# P04_Processor_2_or_3_USB_and_Serial.net
KiCad netlist of a schematic drawn in Altium Designer
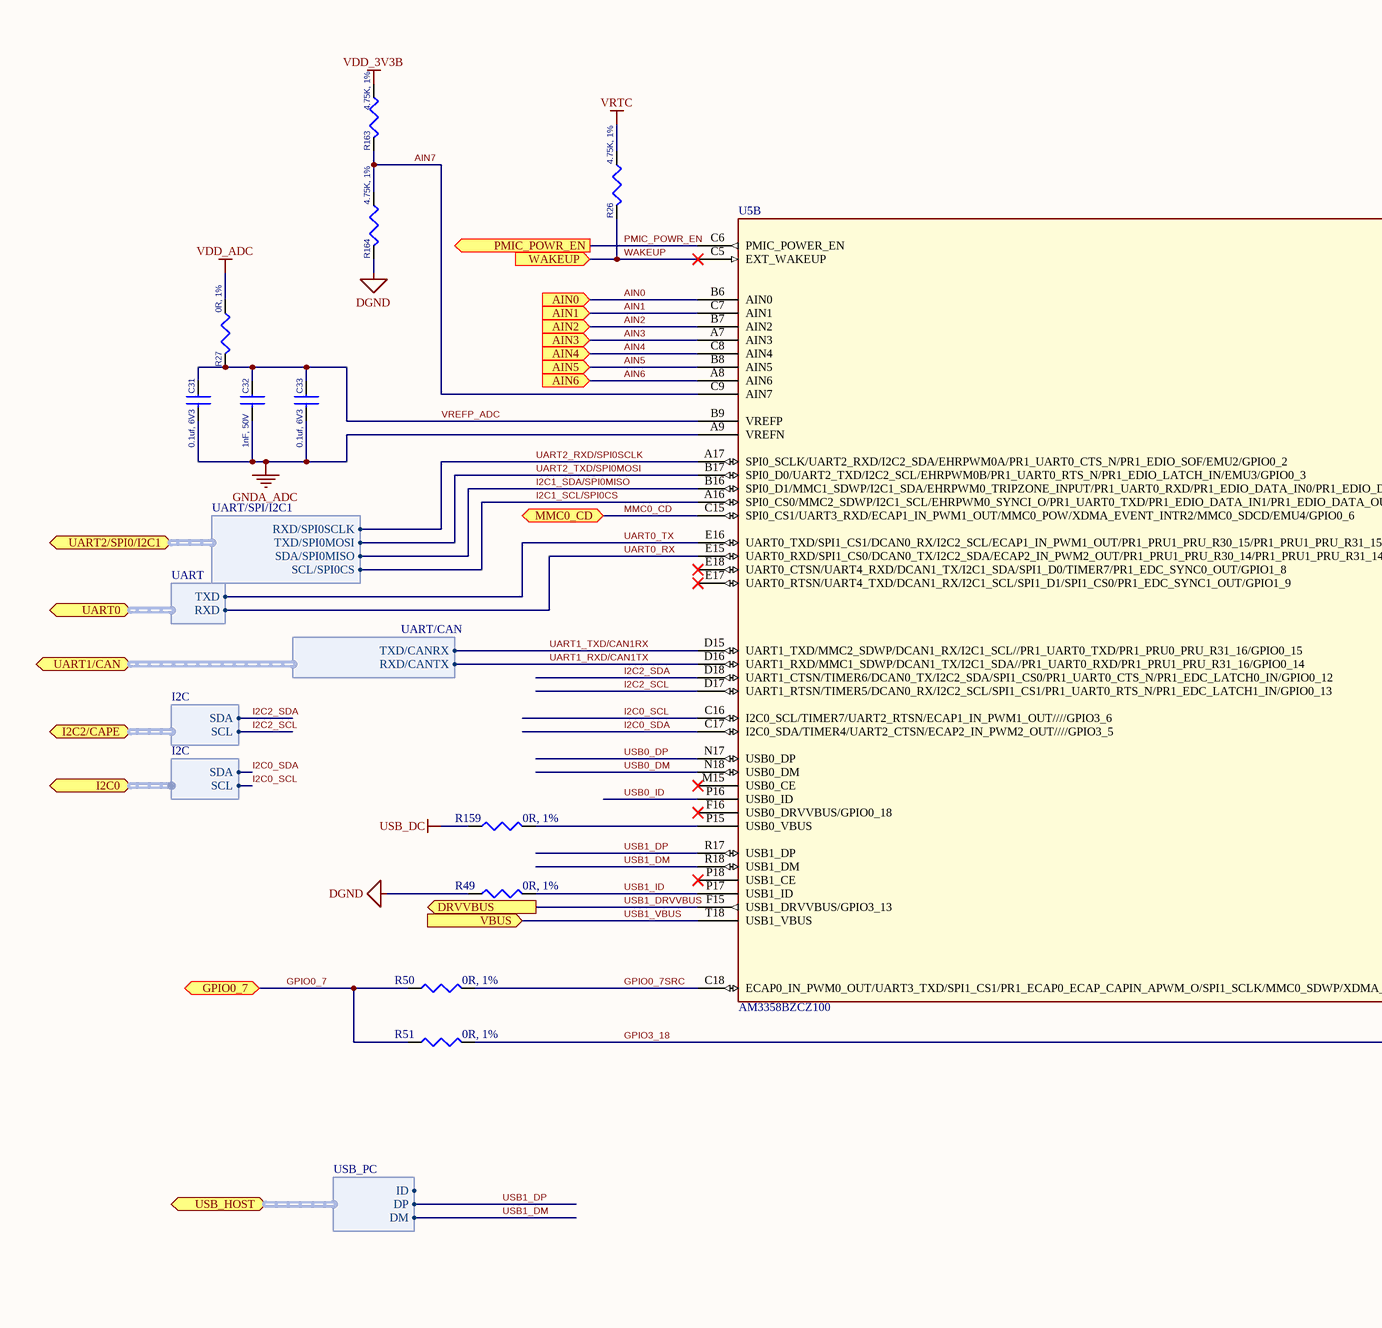
[diagram p0: P04_Processor 2 or 3, USB and Serial.SchDoc, left]
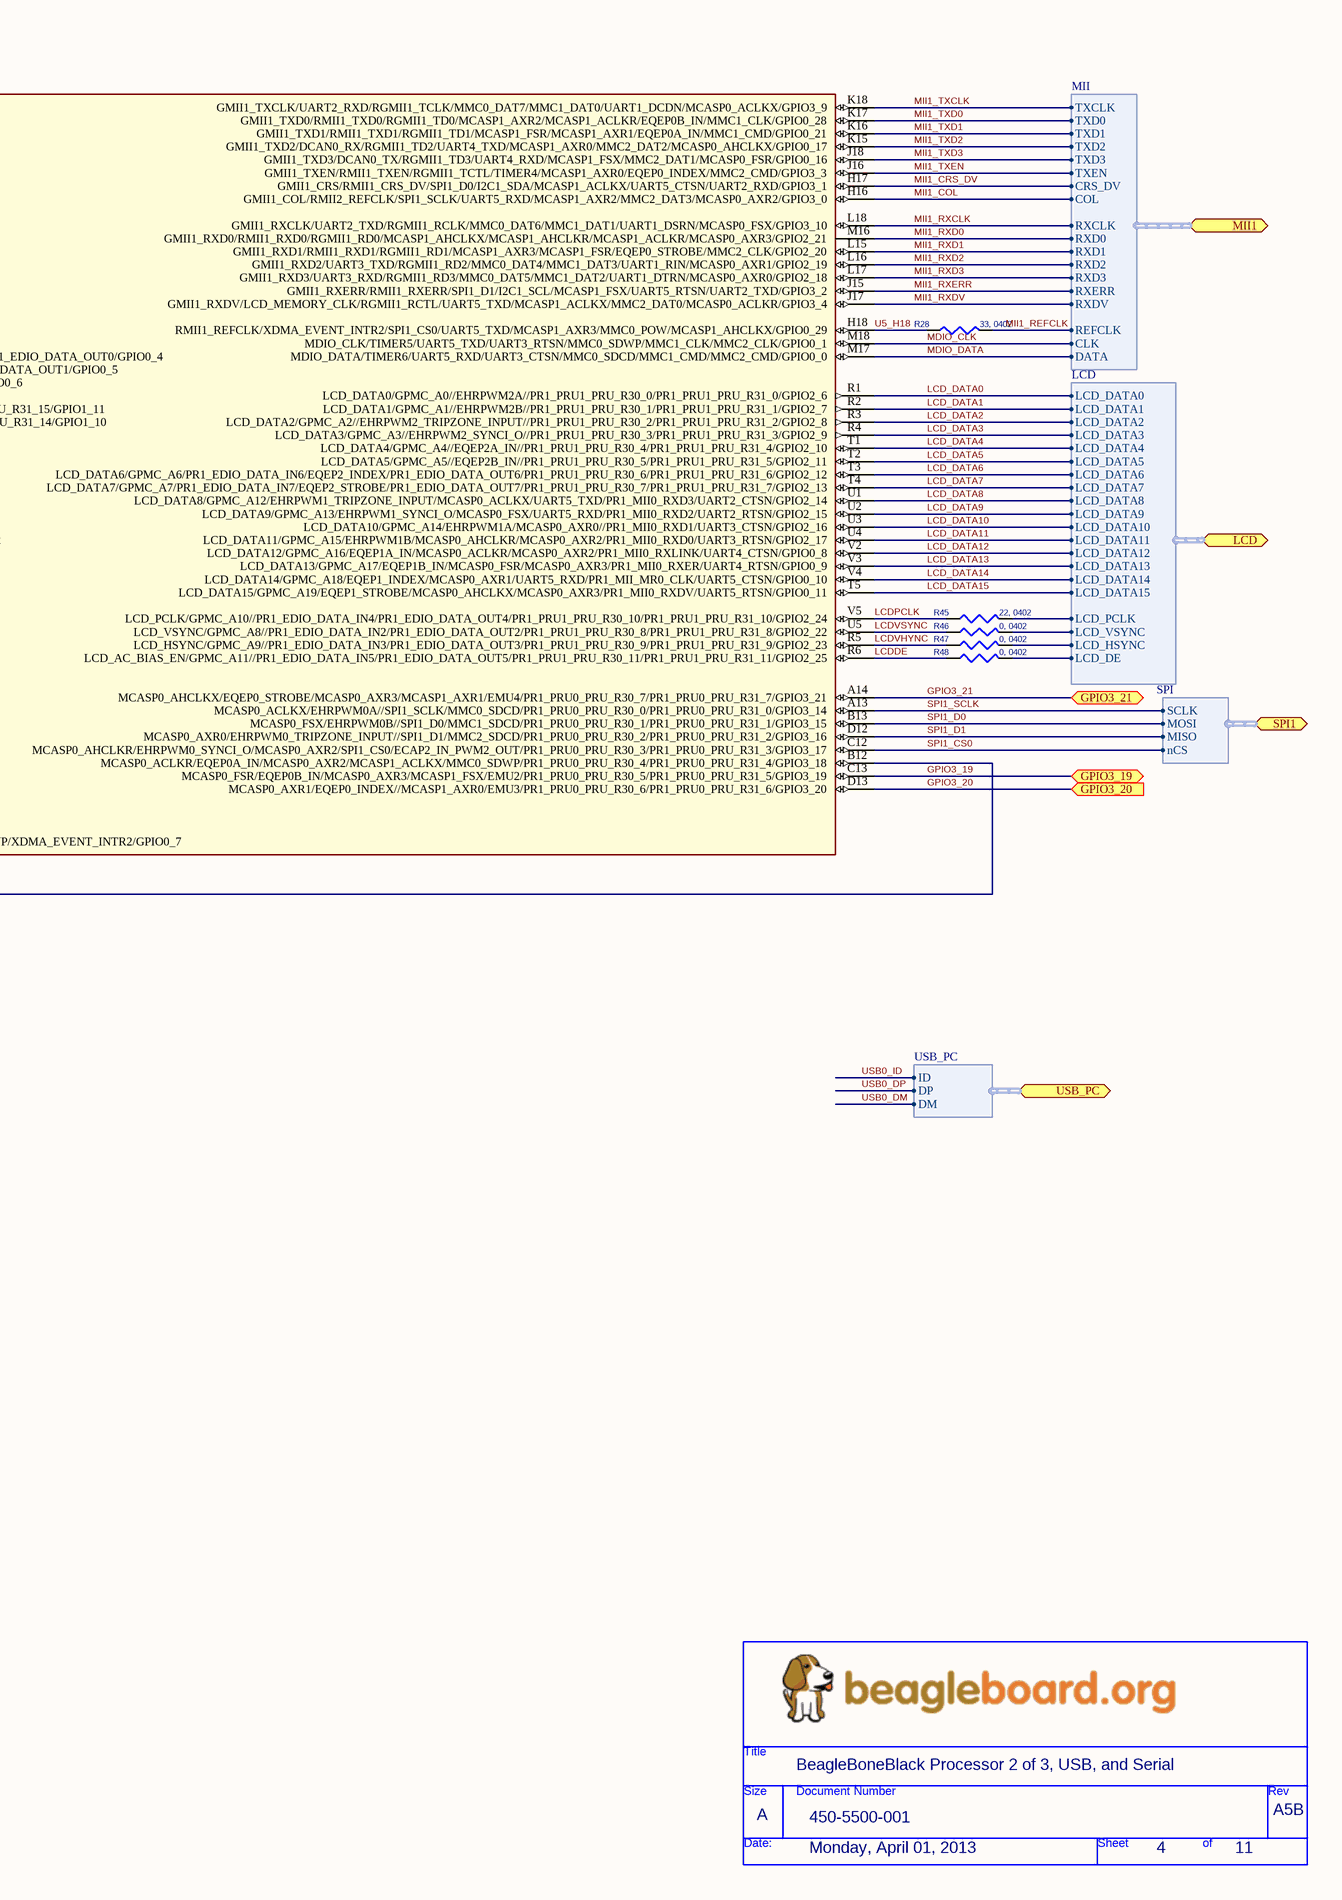
[diagram p1: P04_Processor 2 or 3, USB and Serial.SchDoc, right]

(export (version "E")
  (design (tool "Eeschema 10.0.6"))
  (components
    (comp (ref "C31")
      (value "0.1uf, 6V3")
      (footprint "402")
      (description "CAP CER 0.1UF 6.3V 10% X5R 0402")
      (fields
        (field (name "MANUFACTURER") "TDK Corporation")
        (field (name "MANUFACTURER PART NUMBER") "C1005X5R0J104K050BA")
      )
      (libsource (lib "BEAGLEBONEBLACK_REV A5B") (part "CAP_0.1uF_X7R_16V_10% 0402"))
    )
    (comp (ref "C32")
      (value "1nF, 50V")
      (footprint "402")
      (description "CAP CER 1000PF 16V 10% X7R 0402")
      (fields
        (field (name "MANUFACTURER") "Yageo")
        (field (name "MANUFACTURER PART NUMBER") "CC0402KRX7R7BB102")
      )
      (libsource (lib "BEAGLEBONEBLACK_REV A5B") (part "CAP_0.001_X7R_50V_5%_0402"))
    )
    (comp (ref "C33")
      (value "0.1uf, 6V3")
      (footprint "402")
      (description "CAP CER 0.1UF 6.3V 10% X5R 0402")
      (fields
        (field (name "MANUFACTURER") "TDK Corporation")
        (field (name "MANUFACTURER PART NUMBER") "C1005X5R0J104K050BA")
      )
      (libsource (lib "BEAGLEBONEBLACK_REV A5B") (part "CAP_0.1uF_X7R_16V_10% 0402"))
    )
    (comp (ref "R26")
      (value "4.75K, 1%")
      (footprint "402")
      (description "RES 4.75K OHM 1/16W 1% 0402 SMD")
      (fields
        (field (name "MANUFACTURER") "Stackpole Electronics Inc")
        (field (name "MANUFACTURER PART NUMBER") "RMCF0402FT4K75")
      )
      (libsource (lib "BEAGLEBONEBLACK_REV A5B") (part "RES_4.75K_1/16W_1%_0402"))
    )
    (comp (ref "R27")
      (value "0R, 1%")
      (footprint "402")
      (description "RES 0.0 OHM 1/16W 0402 SMD")
      (fields
        (field (name "MANUFACTURER") "Yageo")
        (field (name "MANUFACTURER PART NUMBER") "RC0402JR-070RL")
      )
      (libsource (lib "BEAGLEBONEBLACK_REV A5B") (part "RES_0_1/16W_1%_0402"))
    )
    (comp (ref "R28")
      (value "33, 0402")
      (footprint "402")
      (description "RES 33 OHM 1/16W 5% 0402 SMD")
      (fields
        (field (name "MANUFACTURER") "Panasonic Electronic Components")
        (field (name "MANUFACTURER PART NUMBER") "ERJ-2GEJ330X")
      )
      (libsource (lib "BEAGLEBONEBLACK_REV A5B") (part "RES_33_0402"))
    )
    (comp (ref "R45")
      (value "22, 0402")
      (footprint "402")
      (description "RES 22 OHM 1/16W 5% 0402 SMD")
      (fields
        (field (name "MANUFACTURER") "Panasonic Electronic Components")
        (field (name "MANUFACTURER PART NUMBER") "ERJ-2GEJ330X")
      )
      (libsource (lib "BEAGLEBONEBLACK_REV A5B") (part "RES_33_0402"))
    )
    (comp (ref "R46")
      (value "0, 0402")
      (footprint "402")
      (description "RES 0 OHM 1/16W 5% 0402 SMD")
      (fields
        (field (name "MANUFACTURER") "Panasonic Electronic Components")
        (field (name "MANUFACTURER PART NUMBER") "ERJ-2GEJ330X")
      )
      (libsource (lib "BEAGLEBONEBLACK_REV A5B") (part "RES_33_0402"))
    )
    (comp (ref "R47")
      (value "0, 0402")
      (footprint "402")
      (description "RES 0 OHM 1/16W 5% 0402 SMD")
      (fields
        (field (name "MANUFACTURER") "Panasonic Electronic Components")
        (field (name "MANUFACTURER PART NUMBER") "ERJ-2GEJ330X")
      )
      (libsource (lib "BEAGLEBONEBLACK_REV A5B") (part "RES_33_0402"))
    )
    (comp (ref "R48")
      (value "0, 0402")
      (footprint "402")
      (description "RES 0 OHM 1/16W 5% 0402 SMD")
      (fields
        (field (name "MANUFACTURER") "Panasonic Electronic Components")
        (field (name "MANUFACTURER PART NUMBER") "ERJ-2GEJ330X")
      )
      (libsource (lib "BEAGLEBONEBLACK_REV A5B") (part "RES_33_0402"))
    )
    (comp (ref "R49")
      (value "0R, 1%")
      (footprint "402")
      (description "RES 0.0 OHM 1/16W 0402 SMD")
      (fields
        (field (name "MANUFACTURER") "Yageo")
        (field (name "MANUFACTURER PART NUMBER") "RC0402JR-070RL")
      )
      (libsource (lib "BEAGLEBONEBLACK_REV A5B") (part "RES_0_1/16W_1%_0402"))
    )
    (comp (ref "R50")
      (value "0R, 1%")
      (footprint "402")
      (description "RES 0.0 OHM 1/16W 0402 SMD")
      (fields
        (field (name "MANUFACTURER") "Yageo")
        (field (name "MANUFACTURER PART NUMBER") "RC0402JR-070RL")
      )
      (libsource (lib "BEAGLEBONEBLACK_REV A5B") (part "RES_0_1/16W_1%_0402"))
    )
    (comp (ref "R51")
      (value "0R, 1%")
      (footprint "402")
      (description "RES 0.0 OHM 1/16W 0402 SMD")
      (fields
        (field (name "MANUFACTURER") "Yageo")
        (field (name "MANUFACTURER PART NUMBER") "RC0402JR-070RL")
      )
      (libsource (lib "BEAGLEBONEBLACK_REV A5B") (part "RES_0_1/16W_1%_0402"))
    )
    (comp (ref "R159")
      (value "0R, 1%")
      (footprint "402")
      (description "RES 0.0 OHM 1/16W 0402 SMD")
      (fields
        (field (name "MANUFACTURER") "Yageo")
        (field (name "MANUFACTURER PART NUMBER") "RC0402JR-070RL")
      )
      (libsource (lib "BEAGLEBONEBLACK_REV A5B") (part "RES_0_1/16W_1%_0402"))
    )
    (comp (ref "R163")
      (value "4.75K, 1%")
      (footprint "402")
      (description "RES 4.75K OHM 1/16W 1% 0402 SMD")
      (fields
        (field (name "MANUFACTURER") "Stackpole Electronics Inc")
        (field (name "MANUFACTURER PART NUMBER") "RMCF0402FT4K75")
      )
      (libsource (lib "BEAGLEBONEBLACK_REV A5B") (part "RES_4.75K_1/16W_1%_0402"))
    )
    (comp (ref "R164")
      (value "4.75K, 1%")
      (footprint "402")
      (description "RES 4.75K OHM 1/16W 1% 0402 SMD")
      (fields
        (field (name "MANUFACTURER") "Stackpole Electronics Inc")
        (field (name "MANUFACTURER PART NUMBER") "RMCF0402FT4K75")
      )
      (libsource (lib "BEAGLEBONEBLACK_REV A5B") (part "RES_4.75K_1/16W_1%_0402"))
    )
    (comp (ref "U5")
      (value "AM3358BZCZ100")
      (footprint "am33xx_15x15")
      (description "IC MPU SITARA 1.0GHZ 324NFBGA")
      (fields (field (name "MFR") "TI") (field (name "TIINTPARTNUMBER") "1A0242"))
      (libsource (lib "BEAGLEBONEBLACK_REV A5B") (part "IC_AM335X_ZCE_1"))
    )
  )
  (nets
    (net (code "9") (name "/AIN0") (class "Default")
      (node (ref "U5") (pin "B6") (pinfunction "AIN0_B6") (pintype "passive"))
    )
    (net (code "10") (name "/AIN1") (class "Default")
      (node (ref "U5") (pin "C7") (pinfunction "AIN1_C7") (pintype "passive"))
    )
    (net (code "11") (name "/AIN2") (class "Default")
      (node (ref "U5") (pin "B7") (pinfunction "AIN2_B7") (pintype "passive"))
    )
    (net (code "12") (name "/AIN3") (class "Default")
      (node (ref "U5") (pin "A7") (pinfunction "AIN3_A7") (pintype "passive"))
    )
    (net (code "13") (name "/AIN4") (class "Default")
      (node (ref "U5") (pin "C8") (pinfunction "AIN4_C8") (pintype "passive"))
    )
    (net (code "14") (name "/AIN5") (class "Default")
      (node (ref "U5") (pin "B8") (pinfunction "AIN5_B8") (pintype "passive"))
    )
    (net (code "15") (name "/AIN6") (class "Default")
      (node (ref "U5") (pin "A8") (pinfunction "AIN6_A8") (pintype "passive"))
    )
    (net (code "16") (name "/AIN7") (class "Default")
      (node (ref "R163") (pin "2") (pinfunction "2_2") (pintype "passive"))
      (node (ref "R164") (pin "1") (pinfunction "1_1") (pintype "passive"))
      (node (ref "U5") (pin "C9") (pinfunction "AIN7_C9") (pintype "passive"))
    )
    (net (code "17") (name "/GPIO0_7") (class "Default")
      (node (ref "R50") (pin "1") (pinfunction "1_1") (pintype "passive"))
      (node (ref "R51") (pin "1") (pinfunction "1_1") (pintype "passive"))
    )
    (net (code "18") (name "/GPIO0_7SRC") (class "Default")
      (node (ref "R50") (pin "2") (pinfunction "2_2") (pintype "passive"))
      (node (ref "U5") (pin "C18") (pinfunction "ECAP0_IN_PWM0_OUT/UART3_TXD/SPI1_CS1/PR1_ECAP0_ECAP_CAPIN_APWM_O/SPI1_SCLK/MMC0_SDWP/XDMA_EVENT_INTR2/GPIO0_7_C18") (pintype "bidirectional"))
    )
    (net (code "19") (name "/GPIO3_18") (class "Default")
      (node (ref "R51") (pin "2") (pinfunction "2_2") (pintype "passive"))
      (node (ref "U5") (pin "B12") (pinfunction "MCASP0_ACLKR/EQEP0A_IN/MCASP0_AXR2/MCASP1_ACLKX/MMC0_SDWP/PR1_PRU0_PRU_R30_4/PR1_PRU0_PRU_R31_4/GPIO3_18_B12") (pintype "bidirectional"))
    )
    (net (code "20") (name "/GPIO3_19") (class "Default")
      (node (ref "U5") (pin "C13") (pinfunction "MCASP0_FSR/EQEP0B_IN/MCASP0_AXR3/MCASP1_FSX/EMU2/PR1_PRU0_PRU_R30_5/PR1_PRU0_PRU_R31_5/GPIO3_19_C13") (pintype "bidirectional"))
    )
    (net (code "21") (name "/GPIO3_20") (class "Default")
      (node (ref "U5") (pin "D13") (pinfunction "MCASP0_AXR1/EQEP0_INDEX//MCASP1_AXR0/EMU3/PR1_PRU0_PRU_R30_6/PR1_PRU0_PRU_R31_6/GPIO3_20_D13") (pintype "bidirectional"))
    )
    (net (code "22") (name "/GPIO3_21") (class "Default")
      (node (ref "U5") (pin "A14") (pinfunction "MCASP0_AHCLKX/EQEP0_STROBE/MCASP0_AXR3/MCASP1_AXR1/EMU4/PR1_PRU0_PRU_R30_7/PR1_PRU0_PRU_R31_7/GPIO3_21_A14") (pintype "bidirectional"))
    )
    (net (code "23") (name "/I2C0_SCL") (class "Default")
      (node (ref "U5") (pin "C16") (pinfunction "I2C0_SCL/TIMER7/UART2_RTSN/ECAP1_IN_PWM1_OUT////GPIO3_6_C16") (pintype "bidirectional"))
    )
    (net (code "24") (name "/I2C0_SDA") (class "Default")
      (node (ref "U5") (pin "C17") (pinfunction "I2C0_SDA/TIMER4/UART2_CTSN/ECAP2_IN_PWM2_OUT////GPIO3_5_C17") (pintype "bidirectional"))
    )
    (net (code "25") (name "/I2C1_SCL{slash}SPI0CS") (class "Default")
      (node (ref "U5") (pin "A16") (pinfunction "SPI0_CS0/MMC2_SDWP/I2C1_SCL/EHRPWM0_SYNCI_O/PR1_UART0_TXD/PR1_EDIO_DATA_IN1/PR1_EDIO_DATA_OUT1/GPIO0_5_A16") (pintype "bidirectional"))
    )
    (net (code "26") (name "/I2C1_SDA{slash}SPI0MISO") (class "Default")
      (node (ref "U5") (pin "B16") (pinfunction "SPI0_D1/MMC1_SDWP/I2C1_SDA/EHRPWM0_TRIPZONE_INPUT/PR1_UART0_RXD/PR1_EDIO_DATA_IN0/PR1_EDIO_DATA_OUT0/GPIO0_4_B16") (pintype "bidirectional"))
    )
    (net (code "27") (name "/I2C2_SCL") (class "Default")
      (node (ref "U5") (pin "D17") (pinfunction "UART1_RTSN/TIMER5/DCAN0_RX/I2C2_SCL/SPI1_CS1/PR1_UART0_RTS_N/PR1_EDC_LATCH1_IN/GPIO0_13_D17") (pintype "bidirectional"))
    )
    (net (code "28") (name "/I2C2_SDA") (class "Default")
      (node (ref "U5") (pin "D18") (pinfunction "UART1_CTSN/TIMER6/DCAN0_TX/I2C2_SDA/SPI1_CS0/PR1_UART0_CTS_N/PR1_EDC_LATCH0_IN/GPIO0_12_D18") (pintype "bidirectional"))
    )
    (net (code "29") (name "/LCDDE") (class "Default")
      (node (ref "R48") (pin "1") (pinfunction "1_1") (pintype "passive"))
      (node (ref "U5") (pin "R6") (pinfunction "LCD_AC_BIAS_EN/GPMC_A11//PR1_EDIO_DATA_IN5/PR1_EDIO_DATA_OUT5/PR1_PRU1_PRU_R30_11/PR1_PRU1_PRU_R31_11/GPIO2_25_R6") (pintype "bidirectional"))
    )
    (net (code "30") (name "/LCDPCLK") (class "Default")
      (node (ref "R45") (pin "1") (pinfunction "1_1") (pintype "passive"))
      (node (ref "U5") (pin "V5") (pinfunction "LCD_PCLK/GPMC_A10//PR1_EDIO_DATA_IN4/PR1_EDIO_DATA_OUT4/PR1_PRU1_PRU_R30_10/PR1_PRU1_PRU_R31_10/GPIO2_24_V5") (pintype "bidirectional"))
    )
    (net (code "31") (name "/LCDVHYNC") (class "Default")
      (node (ref "R47") (pin "1") (pinfunction "1_1") (pintype "passive"))
      (node (ref "U5") (pin "R5") (pinfunction "LCD_HSYNC/GPMC_A9//PR1_EDIO_DATA_IN3/PR1_EDIO_DATA_OUT3/PR1_PRU1_PRU_R30_9/PR1_PRU1_PRU_R31_9/GPIO2_23_R5") (pintype "bidirectional"))
    )
    (net (code "32") (name "/LCDVSYNC") (class "Default")
      (node (ref "R46") (pin "1") (pinfunction "1_1") (pintype "passive"))
      (node (ref "U5") (pin "U5") (pinfunction "LCD_VSYNC/GPMC_A8//PR1_EDIO_DATA_IN2/PR1_EDIO_DATA_OUT2/PR1_PRU1_PRU_R30_8/PR1_PRU1_PRU_R31_8/GPIO2_22_U5") (pintype "bidirectional"))
    )
    (net (code "33") (name "/LCD_DATA0") (class "Default")
      (node (ref "U5") (pin "R1") (pinfunction "LCD_DATA0/GPMC_A0//EHRPWM2A//PR1_PRU1_PRU_R30_0/PR1_PRU1_PRU_R31_0/GPIO2_6_R1") (pintype "output"))
    )
    (net (code "34") (name "/LCD_DATA1") (class "Default")
      (node (ref "U5") (pin "R2") (pinfunction "LCD_DATA1/GPMC_A1//EHRPWM2B//PR1_PRU1_PRU_R30_1/PR1_PRU1_PRU_R31_1/GPIO2_7_R2") (pintype "output"))
    )
    (net (code "35") (name "/LCD_DATA2") (class "Default")
      (node (ref "U5") (pin "R3") (pinfunction "LCD_DATA2/GPMC_A2//EHRPWM2_TRIPZONE_INPUT//PR1_PRU1_PRU_R30_2/PR1_PRU1_PRU_R31_2/GPIO2_8_R3") (pintype "output"))
    )
    (net (code "36") (name "/LCD_DATA3") (class "Default")
      (node (ref "U5") (pin "R4") (pinfunction "LCD_DATA3/GPMC_A3//EHRPWM2_SYNCI_O//PR1_PRU1_PRU_R30_3/PR1_PRU1_PRU_R31_3/GPIO2_9_R4") (pintype "output"))
    )
    (net (code "37") (name "/LCD_DATA4") (class "Default")
      (node (ref "U5") (pin "T1") (pinfunction "LCD_DATA4/GPMC_A4//EQEP2A_IN//PR1_PRU1_PRU_R30_4/PR1_PRU1_PRU_R31_4/GPIO2_10_T1") (pintype "bidirectional"))
    )
    (net (code "38") (name "/LCD_DATA5") (class "Default")
      (node (ref "U5") (pin "T2") (pinfunction "LCD_DATA5/GPMC_A5//EQEP2B_IN//PR1_PRU1_PRU_R30_5/PR1_PRU1_PRU_R31_5/GPIO2_11_T2") (pintype "bidirectional"))
    )
    (net (code "39") (name "/LCD_DATA6") (class "Default")
      (node (ref "U5") (pin "T3") (pinfunction "LCD_DATA6/GPMC_A6/PR1_EDIO_DATA_IN6/EQEP2_INDEX/PR1_EDIO_DATA_OUT6/PR1_PRU1_PRU_R30_6/PR1_PRU1_PRU_R31_6/GPIO2_12_T3") (pintype "bidirectional"))
    )
    (net (code "40") (name "/LCD_DATA7") (class "Default")
      (node (ref "U5") (pin "T4") (pinfunction "LCD_DATA7/GPMC_A7/PR1_EDIO_DATA_IN7/EQEP2_STROBE/PR1_EDIO_DATA_OUT7/PR1_PRU1_PRU_R30_7/PR1_PRU1_PRU_R31_7/GPIO2_13_T4") (pintype "bidirectional"))
    )
    (net (code "41") (name "/LCD_DATA8") (class "Default")
      (node (ref "U5") (pin "U1") (pinfunction "LCD_DATA8/GPMC_A12/EHRPWM1_TRIPZONE_INPUT/MCASP0_ACLKX/UART5_TXD/PR1_MII0_RXD3/UART2_CTSN/GPIO2_14_U1") (pintype "bidirectional"))
    )
    (net (code "42") (name "/LCD_DATA9") (class "Default")
      (node (ref "U5") (pin "U2") (pinfunction "LCD_DATA9/GPMC_A13/EHRPWM1_SYNCI_O/MCASP0_FSX/UART5_RXD/PR1_MII0_RXD2/UART2_RTSN/GPIO2_15_U2") (pintype "bidirectional"))
    )
    (net (code "43") (name "/LCD_DATA10") (class "Default")
      (node (ref "U5") (pin "U3") (pinfunction "LCD_DATA10/GPMC_A14/EHRPWM1A/MCASP0_AXR0//PR1_MII0_RXD1/UART3_CTSN/GPIO2_16_U3") (pintype "bidirectional"))
    )
    (net (code "44") (name "/LCD_DATA11") (class "Default")
      (node (ref "U5") (pin "U4") (pinfunction "LCD_DATA11/GPMC_A15/EHRPWM1B/MCASP0_AHCLKR/MCASP0_AXR2/PR1_MII0_RXD0/UART3_RTSN/GPIO2_17_U4") (pintype "bidirectional"))
    )
    (net (code "45") (name "/LCD_DATA12") (class "Default")
      (node (ref "U5") (pin "V2") (pinfunction "LCD_DATA12/GPMC_A16/EQEP1A_IN/MCASP0_ACLKR/MCASP0_AXR2/PR1_MII0_RXLINK/UART4_CTSN/GPIO0_8_V2") (pintype "bidirectional"))
    )
    (net (code "46") (name "/LCD_DATA13") (class "Default")
      (node (ref "U5") (pin "V3") (pinfunction "LCD_DATA13/GPMC_A17/EQEP1B_IN/MCASP0_FSR/MCASP0_AXR3/PR1_MII0_RXER/UART4_RTSN/GPIO0_9_V3") (pintype "bidirectional"))
    )
    (net (code "47") (name "/LCD_DATA14") (class "Default")
      (node (ref "U5") (pin "V4") (pinfunction "LCD_DATA14/GPMC_A18/EQEP1_INDEX/MCASP0_AXR1/UART5_RXD/PR1_MII_MR0_CLK/UART5_CTSN/GPIO0_10_V4") (pintype "bidirectional"))
    )
    (net (code "48") (name "/LCD_DATA15") (class "Default")
      (node (ref "U5") (pin "T5") (pinfunction "LCD_DATA15/GPMC_A19/EQEP1_STROBE/MCASP0_AHCLKX/MCASP0_AXR3/PR1_MII0_RXDV/UART5_RTSN/GPIO0_11_T5") (pintype "bidirectional"))
    )
    (net (code "49") (name "/LCD_DE") (class "Default")
      (node (ref "R48") (pin "2") (pinfunction "2_2") (pintype "passive"))
    )
    (net (code "50") (name "/LCD_HSYNC") (class "Default")
      (node (ref "R47") (pin "2") (pinfunction "2_2") (pintype "passive"))
    )
    (net (code "51") (name "/LCD_PCLK") (class "Default")
      (node (ref "R45") (pin "2") (pinfunction "2_2") (pintype "passive"))
    )
    (net (code "52") (name "/LCD_VSYNC") (class "Default")
      (node (ref "R46") (pin "2") (pinfunction "2_2") (pintype "passive"))
    )
    (net (code "53") (name "/MDIO_CLK") (class "Default")
      (node (ref "U5") (pin "M18") (pinfunction "MDIO_CLK/TIMER5/UART5_TXD/UART3_RTSN/MMC0_SDWP/MMC1_CLK/MMC2_CLK/GPIO0_1_M18") (pintype "bidirectional"))
    )
    (net (code "54") (name "/MDIO_DATA") (class "Default")
      (node (ref "U5") (pin "M17") (pinfunction "MDIO_DATA/TIMER6/UART5_RXD/UART3_CTSN/MMC0_SDCD/MMC1_CMD/MMC2_CMD/GPIO0_0_M17") (pintype "bidirectional"))
    )
    (net (code "55") (name "/MII1_COL") (class "Default")
      (node (ref "U5") (pin "H16") (pinfunction "GMII1_COL/RMII2_REFCLK/SPI1_SCLK/UART5_RXD/MCASP1_AXR2/MMC2_DAT3/MCASP0_AXR2/GPIO3_0_H16") (pintype "bidirectional"))
    )
    (net (code "56") (name "/MII1_CRS_DV") (class "Default")
      (node (ref "U5") (pin "H17") (pinfunction "GMII1_CRS/RMII1_CRS_DV/SPI1_D0/I2C1_SDA/MCASP1_ACLKX/UART5_CTSN/UART2_RXD/GPIO3_1_H17") (pintype "bidirectional"))
    )
    (net (code "57") (name "/MII1_REFCLK") (class "Default")
      (node (ref "R28") (pin "2") (pinfunction "2_2") (pintype "passive"))
    )
    (net (code "58") (name "/MII1_RXCLK") (class "Default")
      (node (ref "U5") (pin "L18") (pinfunction "GMII1_RXCLK/UART2_TXD/RGMII1_RCLK/MMC0_DAT6/MMC1_DAT1/UART1_DSRN/MCASP0_FSX/GPIO3_10_L18") (pintype "bidirectional"))
    )
    (net (code "59") (name "/MII1_RXD0") (class "Default")
      (node (ref "U5") (pin "M16") (pinfunction "GMII1_RXD0/RMII1_RXD0/RGMII1_RD0/MCASP1_AHCLKX/MCASP1_AHCLKR/MCASP1_ACLKR/MCASP0_AXR3/GPIO2_21_M16") (pintype "passive"))
    )
    (net (code "60") (name "/MII1_RXD1") (class "Default")
      (node (ref "U5") (pin "L15") (pinfunction "GMII1_RXD1/RMII1_RXD1/RGMII1_RD1/MCASP1_AXR3/MCASP1_FSR/EQEP0_STROBE/MMC2_CLK/GPIO2_20_L15") (pintype "bidirectional"))
    )
    (net (code "61") (name "/MII1_RXD2") (class "Default")
      (node (ref "U5") (pin "L16") (pinfunction "GMII1_RXD2/UART3_TXD/RGMII1_RD2/MMC0_DAT4/MMC1_DAT3/UART1_RIN/MCASP0_AXR1/GPIO2_19_L16") (pintype "bidirectional"))
    )
    (net (code "62") (name "/MII1_RXD3") (class "Default")
      (node (ref "U5") (pin "L17") (pinfunction "GMII1_RXD3/UART3_RXD/RGMII1_RD3/MMC0_DAT5/MMC1_DAT2/UART1_DTRN/MCASP0_AXR0/GPIO2_18_L17") (pintype "bidirectional"))
    )
    (net (code "63") (name "/MII1_RXDV") (class "Default")
      (node (ref "U5") (pin "J17") (pinfunction "GMII1_RXDV/LCD_MEMORY_CLK/RGMII1_RCTL/UART5_TXD/MCASP1_ACLKX/MMC2_DAT0/MCASP0_ACLKR/GPIO3_4_J17") (pintype "bidirectional"))
    )
    (net (code "64") (name "/MII1_RXERR") (class "Default")
      (node (ref "U5") (pin "J15") (pinfunction "GMII1_RXERR/RMII1_RXERR/SPI1_D1/I2C1_SCL/MCASP1_FSX/UART5_RTSN/UART2_TXD/GPIO3_2_J15") (pintype "bidirectional"))
    )
    (net (code "65") (name "/MII1_TXCLK") (class "Default")
      (node (ref "U5") (pin "K18") (pinfunction "GMII1_TXCLK/UART2_RXD/RGMII1_TCLK/MMC0_DAT7/MMC1_DAT0/UART1_DCDN/MCASP0_ACLKX/GPIO3_9_K18") (pintype "bidirectional"))
    )
    (net (code "66") (name "/MII1_TXD0") (class "Default")
      (node (ref "U5") (pin "K17") (pinfunction "GMII1_TXD0/RMII1_TXD0/RGMII1_TD0/MCASP1_AXR2/MCASP1_ACLKR/EQEP0B_IN/MMC1_CLK/GPIO0_28_K17") (pintype "bidirectional"))
    )
    (net (code "67") (name "/MII1_TXD1") (class "Default")
      (node (ref "U5") (pin "K16") (pinfunction "GMII1_TXD1/RMII1_TXD1/RGMII1_TD1/MCASP1_FSR/MCASP1_AXR1/EQEP0A_IN/MMC1_CMD/GPIO0_21_K16") (pintype "bidirectional"))
    )
    (net (code "68") (name "/MII1_TXD2") (class "Default")
      (node (ref "U5") (pin "K15") (pinfunction "GMII1_TXD2/DCAN0_RX/RGMII1_TD2/UART4_TXD/MCASP1_AXR0/MMC2_DAT2/MCASP0_AHCLKX/GPIO0_17_K15") (pintype "bidirectional"))
    )
    (net (code "69") (name "/MII1_TXD3") (class "Default")
      (node (ref "U5") (pin "J18") (pinfunction "GMII1_TXD3/DCAN0_TX/RGMII1_TD3/UART4_RXD/MCASP1_FSX/MMC2_DAT1/MCASP0_FSR/GPIO0_16_J18") (pintype "bidirectional"))
    )
    (net (code "70") (name "/MII1_TXEN") (class "Default")
      (node (ref "U5") (pin "J16") (pinfunction "GMII1_TXEN/RMII1_TXEN/RGMII1_TCTL/TIMER4/MCASP1_AXR0/EQEP0_INDEX/MMC2_CMD/GPIO3_3_J16") (pintype "bidirectional"))
    )
    (net (code "71") (name "/MMC0_CD") (class "Default")
      (node (ref "U5") (pin "C15") (pinfunction "SPI0_CS1/UART3_RXD/ECAP1_IN_PWM1_OUT/MMC0_POW/XDMA_EVENT_INTR2/MMC0_SDCD/EMU4/GPIO0_6_C15") (pintype "bidirectional"))
    )
    (net (code "72") (name "/PMIC_POWR_EN") (class "Default")
      (node (ref "U5") (pin "C6") (pinfunction "PMIC_POWER_EN_C6") (pintype "output"))
    )
    (net (code "73") (name "/SPI1_CS0") (class "Default")
      (node (ref "U5") (pin "C12") (pinfunction "MCASP0_AHCLKR/EHRPWM0_SYNCI_O/MCASP0_AXR2/SPI1_CS0/ECAP2_IN_PWM2_OUT/PR1_PRU0_PRU_R30_3/PR1_PRU0_PRU_R31_3/GPIO3_17_C12") (pintype "bidirectional"))
    )
    (net (code "74") (name "/SPI1_D0") (class "Default")
      (node (ref "U5") (pin "B13") (pinfunction "MCASP0_FSX/EHRPWM0B//SPI1_D0/MMC1_SDCD/PR1_PRU0_PRU_R30_1/PR1_PRU0_PRU_R31_1/GPIO3_15_B13") (pintype "bidirectional"))
    )
    (net (code "75") (name "/SPI1_D1") (class "Default")
      (node (ref "U5") (pin "D12") (pinfunction "MCASP0_AXR0/EHRPWM0_TRIPZONE_INPUT//SPI1_D1/MMC2_SDCD/PR1_PRU0_PRU_R30_2/PR1_PRU0_PRU_R31_2/GPIO3_16_D12") (pintype "bidirectional"))
    )
    (net (code "76") (name "/SPI1_SCLK") (class "Default")
      (node (ref "U5") (pin "A13") (pinfunction "MCASP0_ACLKX/EHRPWM0A//SPI1_SCLK/MMC0_SDCD/PR1_PRU0_PRU_R30_0/PR1_PRU0_PRU_R31_0/GPIO3_14_A13") (pintype "bidirectional"))
    )
    (net (code "77") (name "/U5_H18") (class "Default")
      (node (ref "R28") (pin "1") (pinfunction "1_1") (pintype "passive"))
      (node (ref "U5") (pin "H18") (pinfunction "RMII1_REFCLK/XDMA_EVENT_INTR2/SPI1_CS0/UART5_TXD/MCASP1_AXR3/MMC0_POW/MCASP1_AHCLKX/GPIO0_29_H18") (pintype "bidirectional"))
    )
    (net (code "78") (name "/UART0_RX") (class "Default")
      (node (ref "U5") (pin "E15") (pinfunction "UART0_RXD/SPI1_CS0/DCAN0_TX/I2C2_SDA/ECAP2_IN_PWM2_OUT/PR1_PRU1_PRU_R30_14/PR1_PRU1_PRU_R31_14/GPIO1_10_E15") (pintype "bidirectional"))
    )
    (net (code "79") (name "/UART0_TX") (class "Default")
      (node (ref "U5") (pin "E16") (pinfunction "UART0_TXD/SPI1_CS1/DCAN0_RX/I2C2_SCL/ECAP1_IN_PWM1_OUT/PR1_PRU1_PRU_R30_15/PR1_PRU1_PRU_R31_15/GPIO1_11_E16") (pintype "bidirectional"))
    )
    (net (code "80") (name "/UART1_RXD{slash}CAN1TX") (class "Default")
      (node (ref "U5") (pin "D16") (pinfunction "UART1_RXD/MMC1_SDWP/DCAN1_TX/I2C1_SDA//PR1_UART0_RXD/PR1_PRU1_PRU_R31_16/GPIO0_14_D16") (pintype "bidirectional"))
    )
    (net (code "81") (name "/UART1_TXD{slash}CAN1RX") (class "Default")
      (node (ref "U5") (pin "D15") (pinfunction "UART1_TXD/MMC2_SDWP/DCAN1_RX/I2C1_SCL//PR1_UART0_TXD/PR1_PRU0_PRU_R31_16/GPIO0_15_D15") (pintype "bidirectional"))
    )
    (net (code "82") (name "/UART2_RXD{slash}SPI0SCLK") (class "Default")
      (node (ref "U5") (pin "A17") (pinfunction "SPI0_SCLK/UART2_RXD/I2C2_SDA/EHRPWM0A/PR1_UART0_CTS_N/PR1_EDIO_SOF/EMU2/GPIO0_2_A17") (pintype "bidirectional"))
    )
    (net (code "83") (name "/UART2_TXD{slash}SPI0MOSI") (class "Default")
      (node (ref "U5") (pin "B17") (pinfunction "SPI0_D0/UART2_TXD/I2C2_SCL/EHRPWM0B/PR1_UART0_RTS_N/PR1_EDIO_LATCH_IN/EMU3/GPIO0_3_B17") (pintype "bidirectional"))
    )
    (net (code "84") (name "/USB0_DM") (class "Default")
      (node (ref "U5") (pin "N18") (pinfunction "USB0_DM_N18") (pintype "bidirectional"))
    )
    (net (code "85") (name "/USB0_DP") (class "Default")
      (node (ref "U5") (pin "N17") (pinfunction "USB0_DP_N17") (pintype "bidirectional"))
    )
    (net (code "86") (name "/USB0_ID") (class "Default")
      (node (ref "U5") (pin "P16") (pinfunction "USB0_ID_P16") (pintype "passive"))
    )
    (net (code "87") (name "/USB1_DM") (class "Default")
      (node (ref "U5") (pin "R18") (pinfunction "USB1_DM_R18") (pintype "bidirectional"))
    )
    (net (code "88") (name "/USB1_DP") (class "Default")
      (node (ref "U5") (pin "R17") (pinfunction "USB1_DP_R17") (pintype "bidirectional"))
    )
    (net (code "89") (name "/USB1_DRVVBUS") (class "Default")
      (node (ref "U5") (pin "F15") (pinfunction "USB1_DRVVBUS/GPIO3_13_F15") (pintype "output"))
    )
    (net (code "90") (name "/USB1_ID") (class "Default")
      (node (ref "R49") (pin "2") (pinfunction "2_2") (pintype "passive"))
      (node (ref "U5") (pin "P17") (pinfunction "USB1_ID_P17") (pintype "passive"))
    )
    (net (code "91") (name "/USB1_VBUS") (class "Default")
      (node (ref "U5") (pin "T18") (pinfunction "USB1_VBUS_T18") (pintype "passive"))
    )
    (net (code "92") (name "/VREFP_ADC") (class "Default")
      (node (ref "C31") (pin "1") (pinfunction "1_1") (pintype "passive"))
      (node (ref "C32") (pin "1") (pinfunction "1_1") (pintype "passive"))
      (node (ref "C33") (pin "1") (pinfunction "1_1") (pintype "passive"))
      (node (ref "R27") (pin "2") (pinfunction "2_2") (pintype "passive"))
      (node (ref "U5") (pin "B9") (pinfunction "VREFP_B9") (pintype "passive"))
    )
    (net (code "93") (name "/WAKEUP") (class "Default")
      (node (ref "R26") (pin "2") (pinfunction "2_2") (pintype "passive"))
      (node (ref "U5") (pin "C5") (pinfunction "EXT_WAKEUP_C5") (pintype "input"))
    )
    (net (code "102") (name "DGND") (class "Default")
      (node (ref "R164") (pin "2") (pinfunction "2_2") (pintype "passive"))
      (node (ref "R49") (pin "1") (pinfunction "1_1") (pintype "passive"))
    )
    (net (code "103") (name "GNDA_ADC") (class "Default")
      (node (ref "C31") (pin "2") (pinfunction "2_2") (pintype "passive"))
      (node (ref "C32") (pin "2") (pinfunction "2_2") (pintype "passive"))
      (node (ref "C33") (pin "2") (pinfunction "2_2") (pintype "passive"))
      (node (ref "U5") (pin "A9") (pinfunction "VREFN_A9") (pintype "passive"))
    )
    (net (code "104") (name "Net-(U5B-USB0_VBUS)") (class "Default")
      (node (ref "R159") (pin "2") (pinfunction "2_2") (pintype "passive"))
      (node (ref "U5") (pin "P15") (pinfunction "USB0_VBUS_P15") (pintype "passive"))
    )
    (net (code "105") (name "USB_DC") (class "Default")
      (node (ref "R159") (pin "1") (pinfunction "1_1") (pintype "passive"))
    )
    (net (code "106") (name "VDD_3V3B") (class "Default")
      (node (ref "R163") (pin "1") (pinfunction "1_1") (pintype "passive"))
    )
    (net (code "107") (name "VDD_ADC") (class "Default")
      (node (ref "R27") (pin "1") (pinfunction "1_1") (pintype "passive"))
    )
    (net (code "108") (name "VRTC") (class "Default")
      (node (ref "R26") (pin "1") (pinfunction "1_1") (pintype "passive"))
    )
    (net (code "109") (name "unconnected-(U5B-UART0_CTSN{slash}UART4_RXD{slash}DCAN1_TX{slash}I2C1_SDA{slash}SPI1_D0{slash}TIMER7{slash}PR1_EDC_SYNC0_OUT{slash}GPIO1_8-PadE18)") (class "Default")
      (node (ref "U5") (pin "E18") (pinfunction "UART0_CTSN/UART4_RXD/DCAN1_TX/I2C1_SDA/SPI1_D0/TIMER7/PR1_EDC_SYNC0_OUT/GPIO1_8_E18") (pintype "bidirectional+no_connect"))
    )
    (net (code "110") (name "unconnected-(U5B-UART0_RTSN{slash}UART4_TXD{slash}DCAN1_RX{slash}I2C1_SCL{slash}SPI1_D1{slash}SPI1_CS0{slash}PR1_EDC_SYNC1_OUT{slash}GPIO1_9-PadE17)") (class "Default")
      (node (ref "U5") (pin "E17") (pinfunction "UART0_RTSN/UART4_TXD/DCAN1_RX/I2C1_SCL/SPI1_D1/SPI1_CS0/PR1_EDC_SYNC1_OUT/GPIO1_9_E17") (pintype "bidirectional+no_connect"))
    )
    (net (code "111") (name "unconnected-(U5B-USB0_CE-PadM15)") (class "Default")
      (node (ref "U5") (pin "M15") (pinfunction "USB0_CE_M15") (pintype "passive+no_connect"))
    )
    (net (code "112") (name "unconnected-(U5B-USB0_DRVVBUS{slash}GPIO0_18-PadF16)") (class "Default")
      (node (ref "U5") (pin "F16") (pinfunction "USB0_DRVVBUS/GPIO0_18_F16") (pintype "passive+no_connect"))
    )
    (net (code "113") (name "unconnected-(U5B-USB1_CE-PadP18)") (class "Default")
      (node (ref "U5") (pin "P18") (pinfunction "USB1_CE_P18") (pintype "passive+no_connect"))
    )
  )
)
